# SlideBoard.net
KiCad netlist of a schematic drawn in EAGLE
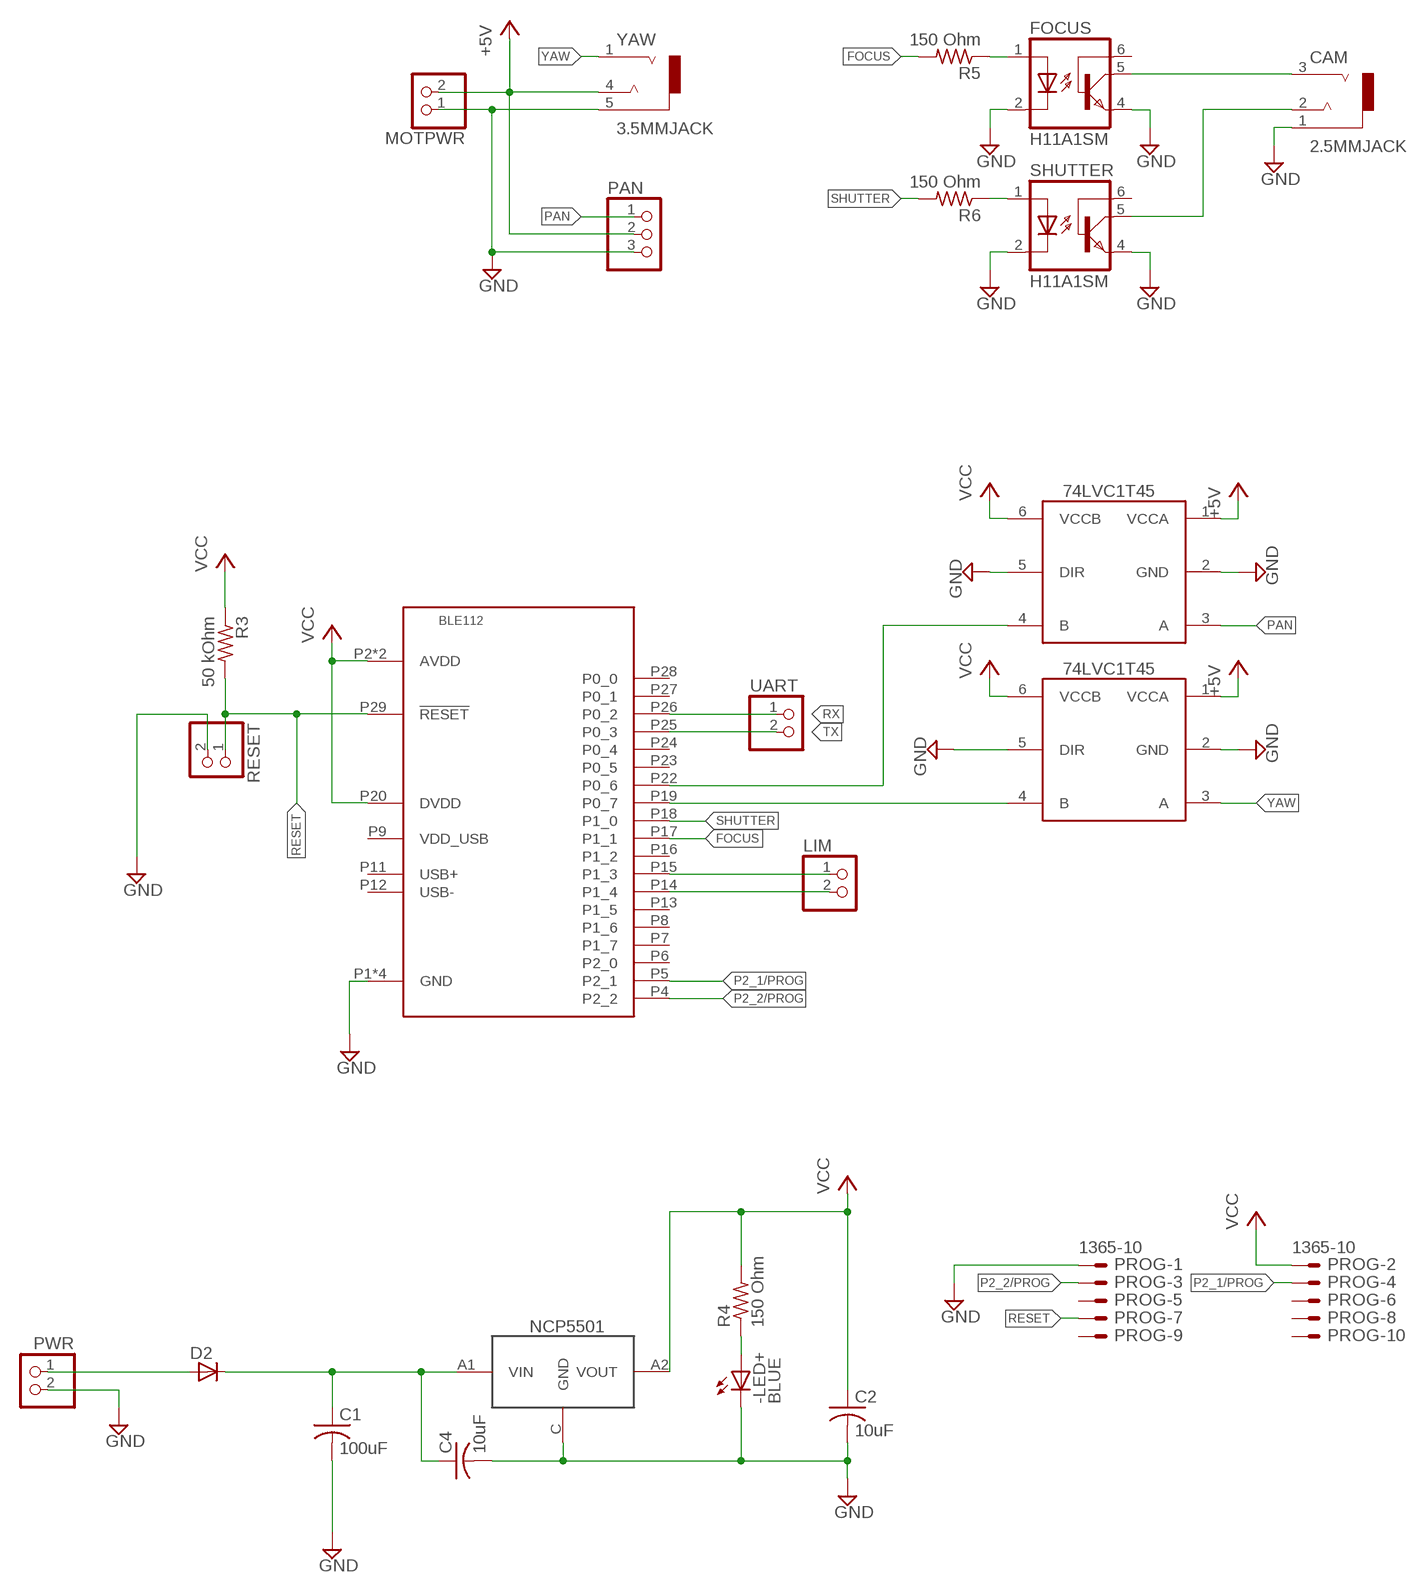
[diagram p0: schematic, sheet 1]

(export (version "E")
  (design (tool "Eeschema 10.0.6"))
  (components
    (comp (ref "-LED+")
      (value "BLUE")
      (footprint "eagle-import:CHIP-LED0603")
      (libsource (lib "eagle-import") (part "LEDCHIP-LED0603"))
    )
    (comp (ref "C1")
      (value "100uF")
      (footprint "eagle-import:C1210")
      (libsource (lib "eagle-import") (part "C-USC1210"))
    )
    (comp (ref "C2")
      (value "10uF")
      (footprint "eagle-import:C0805")
      (libsource (lib "eagle-import") (part "C-USC0805"))
    )
    (comp (ref "C4")
      (value "10uF")
      (footprint "eagle-import:C0805")
      (libsource (lib "eagle-import") (part "C-USC0805"))
    )
    (comp (ref "CAM")
      (value "2.5MMJACK")
      (footprint "eagle-import:2.5MMJACK")
      (libsource (lib "eagle-import") (part "2.5MMJACK"))
    )
    (comp (ref "D2")
      (value "D-A1-C3")
      (footprint "eagle-import:SOT23")
      (libsource (lib "eagle-import") (part "D-A1-C3"))
    )
    (comp (ref "FOCUS")
      (value "H11A1SM")
      (footprint "eagle-import:DIL6-SMD")
      (libsource (lib "eagle-import") (part "H11A?MS1"))
    )
    (comp (ref "LIM")
      (value "PINHD-1X2")
      (footprint "eagle-import:1X02")
      (libsource (lib "eagle-import") (part "PINHD-1X2"))
    )
    (comp (ref "MOTPWR")
      (value "PINHD-1X2")
      (footprint "eagle-import:1X02")
      (libsource (lib "eagle-import") (part "PINHD-1X2"))
    )
    (comp (ref "PAN")
      (value "PINHD-1X3")
      (footprint "eagle-import:1X03")
      (libsource (lib "eagle-import") (part "PINHD-1X3"))
    )
    (comp (ref "PROG")
      (value "1365-10")
      (footprint "eagle-import:1365-10")
      (libsource (lib "eagle-import") (part "1365-10"))
    )
    (comp (ref "PWR")
      (value "PINHD-1X2")
      (footprint "eagle-import:1X02")
      (libsource (lib "eagle-import") (part "PINHD-1X2"))
    )
    (comp (ref "R3")
      (value "50 kOhm")
      (footprint "eagle-import:R0603")
      (libsource (lib "eagle-import") (part "R-US_R0603"))
    )
    (comp (ref "R4")
      (value "150 Ohm")
      (footprint "eagle-import:R0402")
      (libsource (lib "eagle-import") (part "resistor_R-US_R0402"))
    )
    (comp (ref "R5")
      (value "150 Ohm")
      (footprint "eagle-import:R0402")
      (libsource (lib "eagle-import") (part "resistor_R-US_R0402"))
    )
    (comp (ref "R6")
      (value "150 Ohm")
      (footprint "eagle-import:R0402")
      (libsource (lib "eagle-import") (part "resistor_R-US_R0402"))
    )
    (comp (ref "RESET")
      (value "PINHD-1X2")
      (footprint "eagle-import:1X02")
      (libsource (lib "eagle-import") (part "PINHD-1X2"))
    )
    (comp (ref "SHUTTER")
      (value "H11A1SM")
      (footprint "eagle-import:DIL6-SMD")
      (libsource (lib "eagle-import") (part "H11A?MS1"))
    )
    (comp (ref "U$1")
      (value "BLE112")
      (footprint "eagle-import:BLE112")
      (libsource (lib "eagle-import") (part "BLE112"))
    )
    (comp (ref "U$2")
      (value "741T45")
      (footprint "eagle-import:SOT363_PHILIPS")
      (libsource (lib "eagle-import") (part "741T45"))
    )
    (comp (ref "U$3")
      (value "NCP5501")
      (footprint "eagle-import:DPACK_3")
      (libsource (lib "eagle-import") (part "NCP5501"))
    )
    (comp (ref "U$4")
      (value "741T45")
      (footprint "eagle-import:SOT363_PHILIPS")
      (libsource (lib "eagle-import") (part "741T45"))
    )
    (comp (ref "UART")
      (value "PINHD-1X2")
      (footprint "eagle-import:1X02")
      (libsource (lib "eagle-import") (part "PINHD-1X2"))
    )
    (comp (ref "YAW")
      (value "3.5MMJACK")
      (footprint "eagle-import:35RA_SMT")
      (libsource (lib "eagle-import") (part "3.5MMJACK"))
    )
  )
  (nets
    (net (code "1") (name "+5V") (class "Default")
      (node (ref "MOTPWR") (pin "2") (pinfunction "2_2") (pintype "passive"))
      (node (ref "PAN") (pin "2") (pinfunction "2_2") (pintype "passive"))
      (node (ref "U$2") (pin "1") (pinfunction "VCCA_1") (pintype "bidirectional"))
      (node (ref "U$4") (pin "1") (pinfunction "VCCA_1") (pintype "bidirectional"))
      (node (ref "YAW") (pin "4") (pinfunction "4_4") (pintype "passive"))
    )
    (net (code "2") (name "FOCUS") (class "Default")
      (node (ref "R5") (pin "2") (pinfunction "2_2") (pintype "passive"))
      (node (ref "U$1") (pin "P17") (pinfunction "P1_1_P17") (pintype "bidirectional"))
    )
    (net (code "3") (name "GND") (class "Default")
      (node (ref "-LED+") (pin "C") (pinfunction "C_C") (pintype "passive"))
      (node (ref "C1") (pin "2") (pinfunction "2_2") (pintype "passive"))
      (node (ref "C2") (pin "2") (pinfunction "2_2") (pintype "passive"))
      (node (ref "C4") (pin "2") (pinfunction "2_2") (pintype "passive"))
      (node (ref "CAM") (pin "1") (pinfunction "5-GND_1") (pintype "passive"))
      (node (ref "FOCUS") (pin "2") (pinfunction "C_2") (pintype "passive"))
      (node (ref "FOCUS") (pin "4") (pinfunction "EMI_4") (pintype "passive"))
      (node (ref "MOTPWR") (pin "1") (pinfunction "1_1") (pintype "passive"))
      (node (ref "PAN") (pin "3") (pinfunction "3_3") (pintype "passive"))
      (node (ref "PROG") (pin "1") (pinfunction "S_1") (pintype "passive"))
      (node (ref "PWR") (pin "2") (pinfunction "2_2") (pintype "passive"))
      (node (ref "RESET") (pin "2") (pinfunction "2_2") (pintype "passive"))
      (node (ref "SHUTTER") (pin "2") (pinfunction "C_2") (pintype "passive"))
      (node (ref "SHUTTER") (pin "4") (pinfunction "EMI_4") (pintype "passive"))
      (node (ref "U$1") (pin "P1") (pinfunction "GND_P1") (pintype "bidirectional"))
      (node (ref "U$1") (pin "P10") (pinfunction "GND_P10") (pintype "bidirectional"))
      (node (ref "U$1") (pin "P21") (pinfunction "GND_P21") (pintype "bidirectional"))
      (node (ref "U$1") (pin "P30") (pinfunction "GND_P30") (pintype "bidirectional"))
      (node (ref "U$2") (pin "2") (pinfunction "GND_2") (pintype "bidirectional"))
      (node (ref "U$2") (pin "5") (pinfunction "DIR_5") (pintype "bidirectional"))
      (node (ref "U$3") (pin "C") (pinfunction "GND_C") (pintype "bidirectional"))
      (node (ref "U$4") (pin "2") (pinfunction "GND_2") (pintype "bidirectional"))
      (node (ref "U$4") (pin "5") (pinfunction "DIR_5") (pintype "bidirectional"))
      (node (ref "YAW") (pin "5") (pinfunction "5-GND_5") (pintype "passive"))
    )
    (net (code "4") (name "Net-(-LED+-PadA)") (class "Default")
      (node (ref "-LED+") (pin "A") (pinfunction "A_A") (pintype "passive"))
      (node (ref "R4") (pin "1") (pinfunction "1_1") (pintype "passive"))
    )
    (net (code "5") (name "Net-(CAM-1)") (class "Default")
      (node (ref "CAM") (pin "3") (pinfunction "1_3") (pintype "passive"))
      (node (ref "FOCUS") (pin "5") (pinfunction "COL_5") (pintype "passive"))
    )
    (net (code "6") (name "Net-(CAM-4)") (class "Default")
      (node (ref "CAM") (pin "2") (pinfunction "4_2") (pintype "passive"))
      (node (ref "SHUTTER") (pin "5") (pinfunction "COL_5") (pintype "passive"))
    )
    (net (code "7") (name "Net-(D2-A)") (class "Default")
      (node (ref "D2") (pin "1") (pinfunction "A_1") (pintype "passive"))
      (node (ref "PWR") (pin "1") (pinfunction "1_1") (pintype "passive"))
    )
    (net (code "8") (name "Net-(D2-C)") (class "Default")
      (node (ref "C1") (pin "1") (pinfunction "1_1") (pintype "passive"))
      (node (ref "C4") (pin "1") (pinfunction "1_1") (pintype "passive"))
      (node (ref "D2") (pin "3") (pinfunction "C_3") (pintype "passive"))
      (node (ref "U$3") (pin "A1") (pinfunction "VIN_A1") (pintype "bidirectional"))
    )
    (net (code "9") (name "Net-(FOCUS-A)") (class "Default")
      (node (ref "FOCUS") (pin "1") (pinfunction "A_1") (pintype "passive"))
      (node (ref "R5") (pin "1") (pinfunction "1_1") (pintype "passive"))
    )
    (net (code "10") (name "Net-(SHUTTER-A)") (class "Default")
      (node (ref "R6") (pin "1") (pinfunction "1_1") (pintype "passive"))
      (node (ref "SHUTTER") (pin "1") (pinfunction "A_1") (pintype "passive"))
    )
    (net (code "11") (name "Net-(U$1-P0_6)") (class "Default")
      (node (ref "U$1") (pin "P22") (pinfunction "P0_6_P22") (pintype "bidirectional"))
      (node (ref "U$2") (pin "4") (pinfunction "B_4") (pintype "bidirectional"))
    )
    (net (code "12") (name "Net-(U$1-P0_7)") (class "Default")
      (node (ref "U$1") (pin "P19") (pinfunction "P0_7_P19") (pintype "bidirectional"))
      (node (ref "U$4") (pin "4") (pinfunction "B_4") (pintype "bidirectional"))
    )
    (net (code "13") (name "Net-(U$1-P1_3)") (class "Default")
      (node (ref "LIM") (pin "1") (pinfunction "1_1") (pintype "passive"))
      (node (ref "U$1") (pin "P15") (pinfunction "P1_3_P15") (pintype "bidirectional"))
    )
    (net (code "14") (name "Net-(U$1-P1_4)") (class "Default")
      (node (ref "LIM") (pin "2") (pinfunction "2_2") (pintype "passive"))
      (node (ref "U$1") (pin "P14") (pinfunction "P1_4_P14") (pintype "bidirectional"))
    )
    (net (code "15") (name "P2_1{slash}PROG") (class "Default")
      (node (ref "PROG") (pin "4") (pinfunction "S_4") (pintype "passive"))
      (node (ref "U$1") (pin "P5") (pinfunction "P2_1_P5") (pintype "bidirectional"))
    )
    (net (code "16") (name "P2_2{slash}PROG") (class "Default")
      (node (ref "PROG") (pin "3") (pinfunction "S_3") (pintype "passive"))
      (node (ref "U$1") (pin "P4") (pinfunction "P2_2_P4") (pintype "bidirectional"))
    )
    (net (code "17") (name "PAN") (class "Default")
      (node (ref "PAN") (pin "1") (pinfunction "1_1") (pintype "passive"))
      (node (ref "U$2") (pin "3") (pinfunction "A_3") (pintype "bidirectional"))
    )
    (net (code "18") (name "RESET") (class "Default")
      (node (ref "PROG") (pin "7") (pinfunction "S_7") (pintype "passive"))
      (node (ref "R3") (pin "2") (pinfunction "2_2") (pintype "passive"))
      (node (ref "RESET") (pin "1") (pinfunction "1_1") (pintype "passive"))
      (node (ref "U$1") (pin "P29") (pinfunction "~{RESET}_P29") (pintype "bidirectional"))
    )
    (net (code "19") (name "RX") (class "Default")
      (node (ref "U$1") (pin "P26") (pinfunction "P0_2_P26") (pintype "bidirectional"))
      (node (ref "UART") (pin "1") (pinfunction "1_1") (pintype "passive"))
    )
    (net (code "20") (name "SHUTTER") (class "Default")
      (node (ref "R6") (pin "2") (pinfunction "2_2") (pintype "passive"))
      (node (ref "U$1") (pin "P18") (pinfunction "P1_0_P18") (pintype "bidirectional"))
    )
    (net (code "21") (name "TX") (class "Default")
      (node (ref "U$1") (pin "P25") (pinfunction "P0_3_P25") (pintype "bidirectional"))
      (node (ref "UART") (pin "2") (pinfunction "2_2") (pintype "passive"))
    )
    (net (code "22") (name "VCC") (class "Default")
      (node (ref "C2") (pin "1") (pinfunction "1_1") (pintype "passive"))
      (node (ref "PROG") (pin "2") (pinfunction "S_2") (pintype "passive"))
      (node (ref "R3") (pin "1") (pinfunction "1_1") (pintype "passive"))
      (node (ref "R4") (pin "2") (pinfunction "2_2") (pintype "passive"))
      (node (ref "U$1") (pin "P2") (pinfunction "AVDD_P2") (pintype "bidirectional"))
      (node (ref "U$1") (pin "P20") (pinfunction "DVDD_P20") (pintype "bidirectional"))
      (node (ref "U$1") (pin "P3") (pinfunction "AVDD_P3") (pintype "bidirectional"))
      (node (ref "U$2") (pin "6") (pinfunction "VCCB_6") (pintype "bidirectional"))
      (node (ref "U$3") (pin "A2") (pinfunction "VOUT_A2") (pintype "bidirectional"))
      (node (ref "U$4") (pin "6") (pinfunction "VCCB_6") (pintype "bidirectional"))
    )
    (net (code "23") (name "YAW") (class "Default")
      (node (ref "U$4") (pin "3") (pinfunction "A_3") (pintype "bidirectional"))
      (node (ref "YAW") (pin "1") (pinfunction "1_1") (pintype "passive"))
    )
    (net (code "24") (name "unconnected-(FOCUS-BAS-Pad6)") (class "Default")
      (node (ref "FOCUS") (pin "6") (pinfunction "BAS_6") (pintype "passive"))
    )
    (net (code "25") (name "unconnected-(PROGB-S-Pad10)") (class "Default")
      (node (ref "PROG") (pin "10") (pinfunction "S_10") (pintype "passive"))
    )
    (net (code "26") (name "unconnected-(PROGF-S-Pad5)") (class "Default")
      (node (ref "PROG") (pin "5") (pinfunction "S_5") (pintype "passive"))
    )
    (net (code "27") (name "unconnected-(PROGG-S-Pad6)") (class "Default")
      (node (ref "PROG") (pin "6") (pinfunction "S_6") (pintype "passive"))
    )
    (net (code "28") (name "unconnected-(PROGI-S-Pad8)") (class "Default")
      (node (ref "PROG") (pin "8") (pinfunction "S_8") (pintype "passive"))
    )
    (net (code "29") (name "unconnected-(PROGJ-S-Pad9)") (class "Default")
      (node (ref "PROG") (pin "9") (pinfunction "S_9") (pintype "passive"))
    )
    (net (code "30") (name "unconnected-(SHUTTER-BAS-Pad6)") (class "Default")
      (node (ref "SHUTTER") (pin "6") (pinfunction "BAS_6") (pintype "passive"))
    )
    (net (code "31") (name "unconnected-(U$1-P0_0-PadP28)") (class "Default")
      (node (ref "U$1") (pin "P28") (pinfunction "P0_0_P28") (pintype "bidirectional"))
    )
    (net (code "32") (name "unconnected-(U$1-P0_1-PadP27)") (class "Default")
      (node (ref "U$1") (pin "P27") (pinfunction "P0_1_P27") (pintype "bidirectional"))
    )
    (net (code "33") (name "unconnected-(U$1-P0_4-PadP24)") (class "Default")
      (node (ref "U$1") (pin "P24") (pinfunction "P0_4_P24") (pintype "bidirectional"))
    )
    (net (code "34") (name "unconnected-(U$1-P0_5-PadP23)") (class "Default")
      (node (ref "U$1") (pin "P23") (pinfunction "P0_5_P23") (pintype "bidirectional"))
    )
    (net (code "35") (name "unconnected-(U$1-P1_2-PadP16)") (class "Default")
      (node (ref "U$1") (pin "P16") (pinfunction "P1_2_P16") (pintype "bidirectional"))
    )
    (net (code "36") (name "unconnected-(U$1-P1_5-PadP13)") (class "Default")
      (node (ref "U$1") (pin "P13") (pinfunction "P1_5_P13") (pintype "bidirectional"))
    )
    (net (code "37") (name "unconnected-(U$1-P1_6-PadP8)") (class "Default")
      (node (ref "U$1") (pin "P8") (pinfunction "P1_6_P8") (pintype "bidirectional"))
    )
    (net (code "38") (name "unconnected-(U$1-P1_7-PadP7)") (class "Default")
      (node (ref "U$1") (pin "P7") (pinfunction "P1_7_P7") (pintype "bidirectional"))
    )
    (net (code "39") (name "unconnected-(U$1-P2_0-PadP6)") (class "Default")
      (node (ref "U$1") (pin "P6") (pinfunction "P2_0_P6") (pintype "bidirectional"))
    )
    (net (code "40") (name "unconnected-(U$1-USB+-PadP11)") (class "Default")
      (node (ref "U$1") (pin "P11") (pinfunction "USB+_P11") (pintype "bidirectional"))
    )
    (net (code "41") (name "unconnected-(U$1-USB--PadP12)") (class "Default")
      (node (ref "U$1") (pin "P12") (pinfunction "USB-_P12") (pintype "bidirectional"))
    )
    (net (code "42") (name "unconnected-(U$1-VDD_USB-PadP9)") (class "Default")
      (node (ref "U$1") (pin "P9") (pinfunction "VDD_USB_P9") (pintype "bidirectional"))
    )
  )
)
